# Traffic-tracker.net
KiCad netlist of a schematic drawn in EAGLE
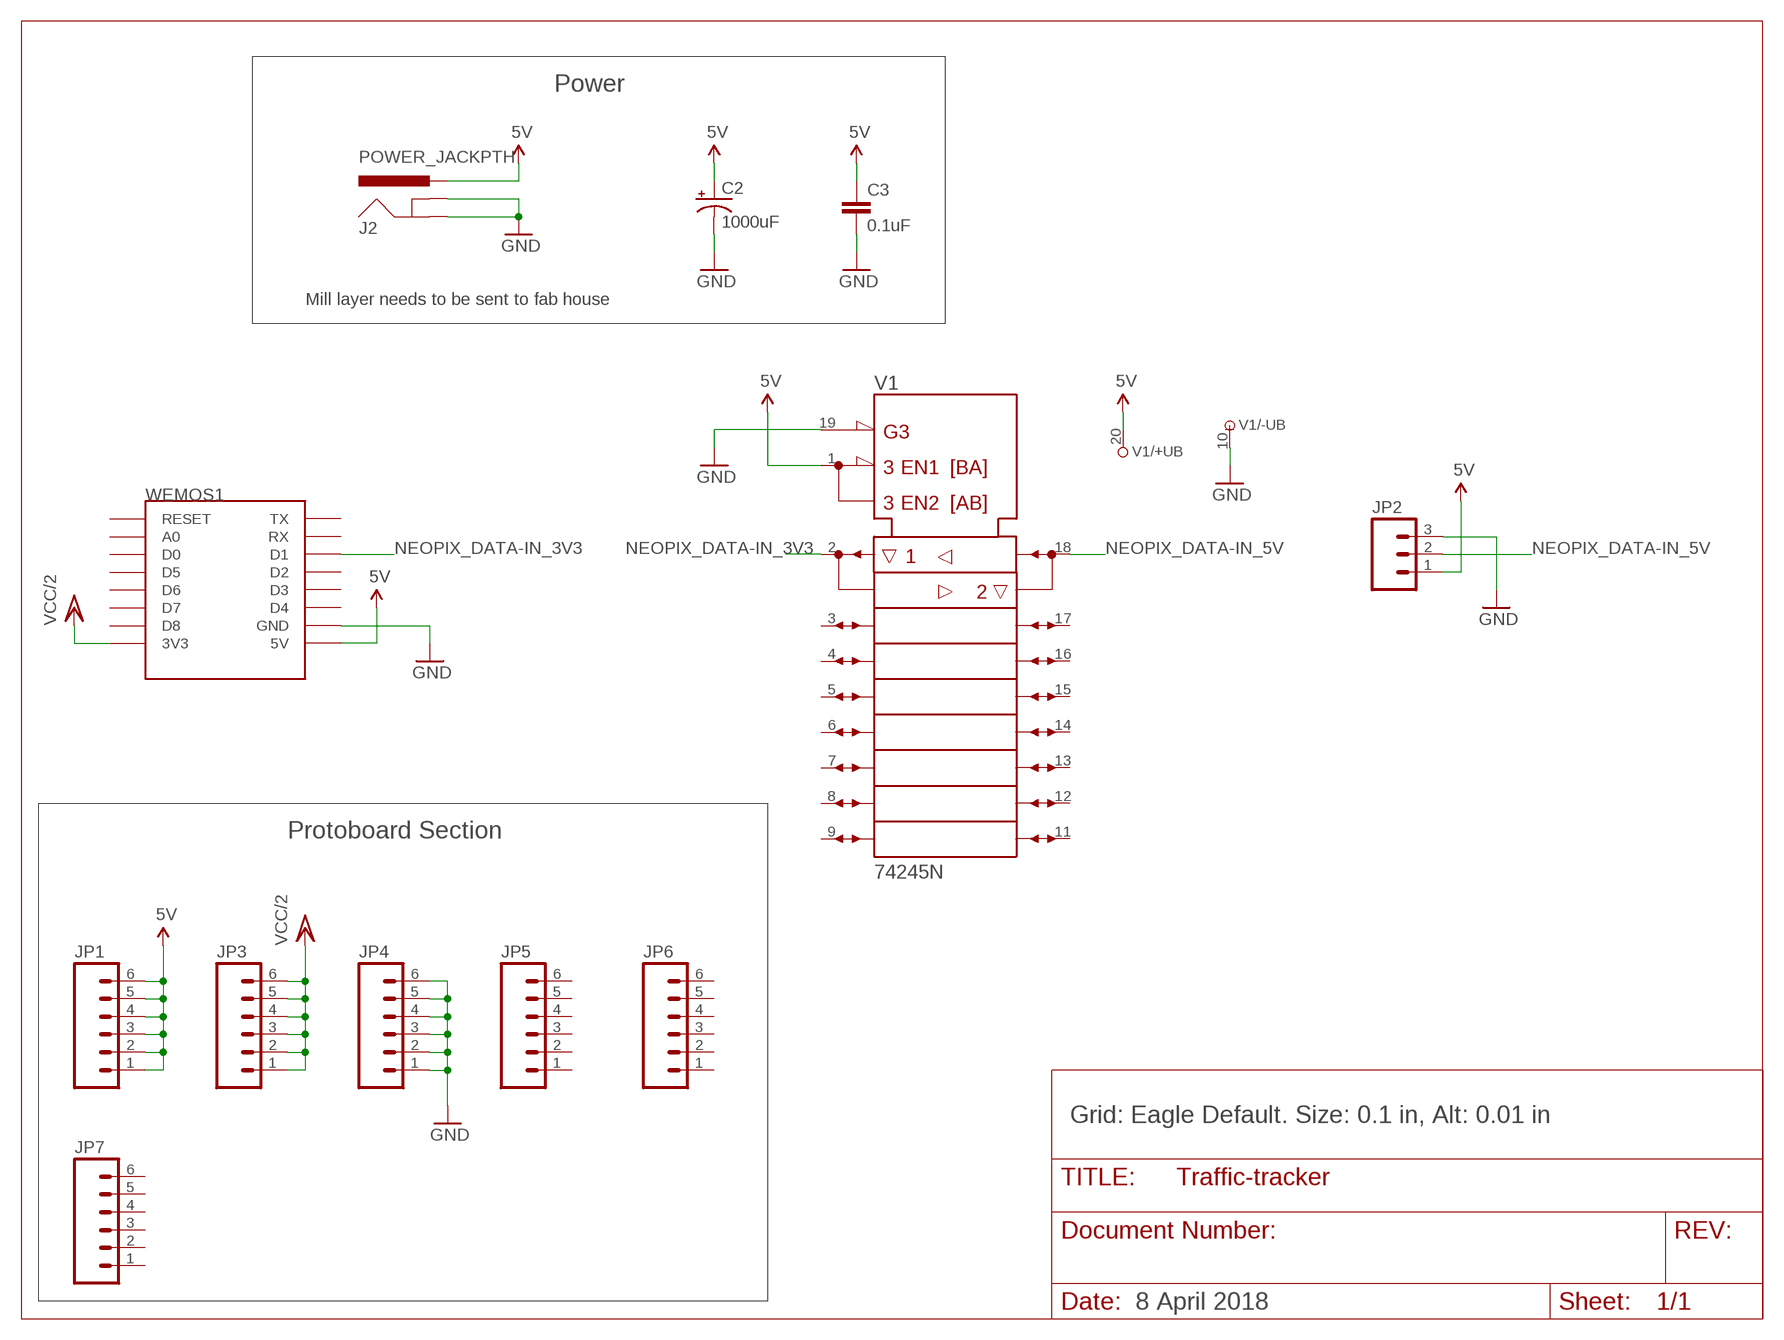
[diagram p0: schematic, sheet 1]

(export (version "E")
  (design (tool "Eeschema 10.0.6"))
  (components
    (comp (ref "C2")
      (value "1000uF")
      (footprint "eagle-import:CPOL-RADIAL-1000UF-25V")
      (libsource (lib "eagle-import") (part "CAP_POLPTH4"))
    )
    (comp (ref "C3")
      (value "0.1uF")
      (footprint "eagle-import:0603-CAP")
      (libsource (lib "eagle-import") (part "CAP0603-CAP"))
    )
    (comp (ref "J2")
      (value "POWER_JACKPTH")
      (footprint "eagle-import:POWER_JACK_PTH")
      (libsource (lib "eagle-import") (part "POWER_JACKPTH"))
    )
    (comp (ref "JP1")
      (value "M06POGOPIN_HOLES_ONLY")
      (footprint "eagle-import:1X06_HOLES_ONLY")
      (libsource (lib "eagle-import") (part "M06POGOPIN_HOLES_ONLY"))
    )
    (comp (ref "JP2")
      (value "M03-SCREW-5MM")
      (footprint "eagle-import:SCREWTERMINAL-5MM-3")
      (libsource (lib "eagle-import") (part "M03-SCREW-5MM"))
    )
    (comp (ref "JP3")
      (value "M06POGOPIN_HOLES_ONLY")
      (footprint "eagle-import:1X06_HOLES_ONLY")
      (libsource (lib "eagle-import") (part "M06POGOPIN_HOLES_ONLY"))
    )
    (comp (ref "JP4")
      (value "M06POGOPIN_HOLES_ONLY")
      (footprint "eagle-import:1X06_HOLES_ONLY")
      (libsource (lib "eagle-import") (part "M06POGOPIN_HOLES_ONLY"))
    )
    (comp (ref "JP5")
      (value "M06POGOPIN_HOLES_ONLY")
      (footprint "eagle-import:1X06_HOLES_ONLY")
      (libsource (lib "eagle-import") (part "M06POGOPIN_HOLES_ONLY"))
    )
    (comp (ref "JP6")
      (value "M06POGOPIN_HOLES_ONLY")
      (footprint "eagle-import:1X06_HOLES_ONLY")
      (libsource (lib "eagle-import") (part "M06POGOPIN_HOLES_ONLY"))
    )
    (comp (ref "JP7")
      (value "M06POGOPIN_HOLES_ONLY")
      (footprint "eagle-import:1X06_HOLES_ONLY")
      (libsource (lib "eagle-import") (part "M06POGOPIN_HOLES_ONLY"))
    )
    (comp (ref "V1")
      (value "74245N")
      (footprint "eagle-import:DIL20")
      (libsource (lib "eagle-import") (part "74245N"))
    )
    (comp (ref "WEMOS1")
      (value "WEMOS-D1-MINI")
      (footprint "eagle-import:WEMOS-D1-MINI")
      (libsource (lib "eagle-import") (part "WEMOS-D1-MINI"))
    )
  )
  (nets
    (net (code "1") (name "/NEOPIX_DATA-IN_3V3") (class "Default")
      (node (ref "V1") (pin "2") (pinfunction "A1_2") (pintype "bidirectional"))
      (node (ref "WEMOS1") (pin "D1") (pinfunction "D1_D1") (pintype "bidirectional"))
    )
    (net (code "2") (name "/NEOPIX_DATA-IN_5V") (class "Default")
      (node (ref "JP2") (pin "2") (pinfunction "2_2") (pintype "passive"))
      (node (ref "V1") (pin "18") (pinfunction "B1_18") (pintype "bidirectional"))
    )
    (net (code "3") (name "5V") (class "Default")
      (node (ref "C2") (pin "1") (pinfunction "+_1") (pintype "passive"))
      (node (ref "C3") (pin "1") (pinfunction "1_1") (pintype "passive"))
      (node (ref "J2") (pin "PWR") (pinfunction "PWR_PWR") (pintype "bidirectional"))
      (node (ref "JP1") (pin "1") (pinfunction "1_1") (pintype "passive"))
      (node (ref "JP1") (pin "2") (pinfunction "2_2") (pintype "passive"))
      (node (ref "JP1") (pin "3") (pinfunction "3_3") (pintype "passive"))
      (node (ref "JP1") (pin "4") (pinfunction "4_4") (pintype "passive"))
      (node (ref "JP1") (pin "5") (pinfunction "5_5") (pintype "passive"))
      (node (ref "JP1") (pin "6") (pinfunction "6_6") (pintype "passive"))
      (node (ref "JP2") (pin "1") (pinfunction "1_1") (pintype "passive"))
      (node (ref "V1") (pin "1") (pinfunction "DIR_1") (pintype "input"))
      (node (ref "V1") (pin "20") (pinfunction "+UB_20") (pintype "power_in"))
      (node (ref "WEMOS1") (pin "5V") (pinfunction "5V_5V") (pintype "bidirectional"))
    )
    (net (code "4") (name "GND") (class "Default")
      (node (ref "C2") (pin "2") (pinfunction "-_2") (pintype "passive"))
      (node (ref "C3") (pin "2") (pinfunction "2_2") (pintype "passive"))
      (node (ref "J2") (pin "GND") (pinfunction "GND_GND") (pintype "bidirectional"))
      (node (ref "J2") (pin "GNDBREAK") (pinfunction "GNDBREAK_GNDBREAK") (pintype "bidirectional"))
      (node (ref "JP2") (pin "3") (pinfunction "3_3") (pintype "passive"))
      (node (ref "JP4") (pin "1") (pinfunction "1_1") (pintype "passive"))
      (node (ref "JP4") (pin "2") (pinfunction "2_2") (pintype "passive"))
      (node (ref "JP4") (pin "3") (pinfunction "3_3") (pintype "passive"))
      (node (ref "JP4") (pin "4") (pinfunction "4_4") (pintype "passive"))
      (node (ref "JP4") (pin "5") (pinfunction "5_5") (pintype "passive"))
      (node (ref "JP4") (pin "6") (pinfunction "6_6") (pintype "passive"))
      (node (ref "V1") (pin "10") (pinfunction "-UB_10") (pintype "power_in"))
      (node (ref "V1") (pin "19") (pinfunction "~{G}_19") (pintype "input"))
      (node (ref "WEMOS1") (pin "GND") (pinfunction "GND_GND") (pintype "bidirectional"))
    )
    (net (code "5") (name "VCC{slash}2") (class "Default")
      (node (ref "JP3") (pin "1") (pinfunction "1_1") (pintype "passive"))
      (node (ref "JP3") (pin "2") (pinfunction "2_2") (pintype "passive"))
      (node (ref "JP3") (pin "3") (pinfunction "3_3") (pintype "passive"))
      (node (ref "JP3") (pin "4") (pinfunction "4_4") (pintype "passive"))
      (node (ref "JP3") (pin "5") (pinfunction "5_5") (pintype "passive"))
      (node (ref "JP3") (pin "6") (pinfunction "6_6") (pintype "passive"))
      (node (ref "WEMOS1") (pin "3V3") (pinfunction "3V3_3V3") (pintype "bidirectional"))
    )
    (net (code "6") (name "unconnected-(JP5-Pad1)") (class "Default")
      (node (ref "JP5") (pin "1") (pinfunction "1_1") (pintype "passive"))
    )
    (net (code "7") (name "unconnected-(JP5-Pad2)") (class "Default")
      (node (ref "JP5") (pin "2") (pinfunction "2_2") (pintype "passive"))
    )
    (net (code "8") (name "unconnected-(JP5-Pad3)") (class "Default")
      (node (ref "JP5") (pin "3") (pinfunction "3_3") (pintype "passive"))
    )
    (net (code "9") (name "unconnected-(JP5-Pad4)") (class "Default")
      (node (ref "JP5") (pin "4") (pinfunction "4_4") (pintype "passive"))
    )
    (net (code "10") (name "unconnected-(JP5-Pad5)") (class "Default")
      (node (ref "JP5") (pin "5") (pinfunction "5_5") (pintype "passive"))
    )
    (net (code "11") (name "unconnected-(JP5-Pad6)") (class "Default")
      (node (ref "JP5") (pin "6") (pinfunction "6_6") (pintype "passive"))
    )
    (net (code "12") (name "unconnected-(JP6-Pad1)") (class "Default")
      (node (ref "JP6") (pin "1") (pinfunction "1_1") (pintype "passive"))
    )
    (net (code "13") (name "unconnected-(JP6-Pad2)") (class "Default")
      (node (ref "JP6") (pin "2") (pinfunction "2_2") (pintype "passive"))
    )
    (net (code "14") (name "unconnected-(JP6-Pad3)") (class "Default")
      (node (ref "JP6") (pin "3") (pinfunction "3_3") (pintype "passive"))
    )
    (net (code "15") (name "unconnected-(JP6-Pad4)") (class "Default")
      (node (ref "JP6") (pin "4") (pinfunction "4_4") (pintype "passive"))
    )
    (net (code "16") (name "unconnected-(JP6-Pad5)") (class "Default")
      (node (ref "JP6") (pin "5") (pinfunction "5_5") (pintype "passive"))
    )
    (net (code "17") (name "unconnected-(JP6-Pad6)") (class "Default")
      (node (ref "JP6") (pin "6") (pinfunction "6_6") (pintype "passive"))
    )
    (net (code "18") (name "unconnected-(JP7-Pad1)") (class "Default")
      (node (ref "JP7") (pin "1") (pinfunction "1_1") (pintype "passive"))
    )
    (net (code "19") (name "unconnected-(JP7-Pad2)") (class "Default")
      (node (ref "JP7") (pin "2") (pinfunction "2_2") (pintype "passive"))
    )
    (net (code "20") (name "unconnected-(JP7-Pad3)") (class "Default")
      (node (ref "JP7") (pin "3") (pinfunction "3_3") (pintype "passive"))
    )
    (net (code "21") (name "unconnected-(JP7-Pad4)") (class "Default")
      (node (ref "JP7") (pin "4") (pinfunction "4_4") (pintype "passive"))
    )
    (net (code "22") (name "unconnected-(JP7-Pad5)") (class "Default")
      (node (ref "JP7") (pin "5") (pinfunction "5_5") (pintype "passive"))
    )
    (net (code "23") (name "unconnected-(JP7-Pad6)") (class "Default")
      (node (ref "JP7") (pin "6") (pinfunction "6_6") (pintype "passive"))
    )
    (net (code "24") (name "unconnected-(V1C-A2-Pad3)") (class "Default")
      (node (ref "V1") (pin "3") (pinfunction "A2_3") (pintype "bidirectional"))
    )
    (net (code "25") (name "unconnected-(V1C-A3-Pad4)") (class "Default")
      (node (ref "V1") (pin "4") (pinfunction "A3_4") (pintype "bidirectional"))
    )
    (net (code "26") (name "unconnected-(V1C-A4-Pad5)") (class "Default")
      (node (ref "V1") (pin "5") (pinfunction "A4_5") (pintype "bidirectional"))
    )
    (net (code "27") (name "unconnected-(V1C-A5-Pad6)") (class "Default")
      (node (ref "V1") (pin "6") (pinfunction "A5_6") (pintype "bidirectional"))
    )
    (net (code "28") (name "unconnected-(V1C-A6-Pad7)") (class "Default")
      (node (ref "V1") (pin "7") (pinfunction "A6_7") (pintype "bidirectional"))
    )
    (net (code "29") (name "unconnected-(V1C-A7-Pad8)") (class "Default")
      (node (ref "V1") (pin "8") (pinfunction "A7_8") (pintype "bidirectional"))
    )
    (net (code "30") (name "unconnected-(V1C-A8-Pad9)") (class "Default")
      (node (ref "V1") (pin "9") (pinfunction "A8_9") (pintype "bidirectional"))
    )
    (net (code "31") (name "unconnected-(V1C-B2-Pad17)") (class "Default")
      (node (ref "V1") (pin "17") (pinfunction "B2_17") (pintype "bidirectional"))
    )
    (net (code "32") (name "unconnected-(V1C-B3-Pad16)") (class "Default")
      (node (ref "V1") (pin "16") (pinfunction "B3_16") (pintype "bidirectional"))
    )
    (net (code "33") (name "unconnected-(V1C-B4-Pad15)") (class "Default")
      (node (ref "V1") (pin "15") (pinfunction "B4_15") (pintype "bidirectional"))
    )
    (net (code "34") (name "unconnected-(V1C-B5-Pad14)") (class "Default")
      (node (ref "V1") (pin "14") (pinfunction "B5_14") (pintype "bidirectional"))
    )
    (net (code "35") (name "unconnected-(V1C-B6-Pad13)") (class "Default")
      (node (ref "V1") (pin "13") (pinfunction "B6_13") (pintype "bidirectional"))
    )
    (net (code "36") (name "unconnected-(V1C-B7-Pad12)") (class "Default")
      (node (ref "V1") (pin "12") (pinfunction "B7_12") (pintype "bidirectional"))
    )
    (net (code "37") (name "unconnected-(V1C-B8-Pad11)") (class "Default")
      (node (ref "V1") (pin "11") (pinfunction "B8_11") (pintype "bidirectional"))
    )
    (net (code "38") (name "unconnected-(WEMOS1-PadA0)") (class "Default")
      (node (ref "WEMOS1") (pin "A0") (pinfunction "A0_A0") (pintype "bidirectional"))
    )
    (net (code "39") (name "unconnected-(WEMOS1-PadD0)") (class "Default")
      (node (ref "WEMOS1") (pin "D0") (pinfunction "D0_D0") (pintype "bidirectional"))
    )
    (net (code "40") (name "unconnected-(WEMOS1-PadD2)") (class "Default")
      (node (ref "WEMOS1") (pin "D2") (pinfunction "D2_D2") (pintype "bidirectional"))
    )
    (net (code "41") (name "unconnected-(WEMOS1-PadD3)") (class "Default")
      (node (ref "WEMOS1") (pin "D3") (pinfunction "D3_D3") (pintype "bidirectional"))
    )
    (net (code "42") (name "unconnected-(WEMOS1-PadD4)") (class "Default")
      (node (ref "WEMOS1") (pin "D4") (pinfunction "D4_D4") (pintype "bidirectional"))
    )
    (net (code "43") (name "unconnected-(WEMOS1-PadD5)") (class "Default")
      (node (ref "WEMOS1") (pin "D5") (pinfunction "D5_D5") (pintype "bidirectional"))
    )
    (net (code "44") (name "unconnected-(WEMOS1-PadD6)") (class "Default")
      (node (ref "WEMOS1") (pin "D6") (pinfunction "D6_D6") (pintype "bidirectional"))
    )
    (net (code "45") (name "unconnected-(WEMOS1-PadD7)") (class "Default")
      (node (ref "WEMOS1") (pin "D7") (pinfunction "D7_D7") (pintype "bidirectional"))
    )
    (net (code "46") (name "unconnected-(WEMOS1-PadD8)") (class "Default")
      (node (ref "WEMOS1") (pin "D8") (pinfunction "D8_D8") (pintype "bidirectional"))
    )
    (net (code "47") (name "unconnected-(WEMOS1-PadRESET)") (class "Default")
      (node (ref "WEMOS1") (pin "RESET") (pinfunction "RESET_RESET") (pintype "bidirectional"))
    )
    (net (code "48") (name "unconnected-(WEMOS1-PadRX)") (class "Default")
      (node (ref "WEMOS1") (pin "RX") (pinfunction "RX_RX") (pintype "bidirectional"))
    )
    (net (code "49") (name "unconnected-(WEMOS1-PadTX)") (class "Default")
      (node (ref "WEMOS1") (pin "TX") (pinfunction "TX_TX") (pintype "bidirectional"))
    )
  )
)
